# debug.net
KiCad netlist of a schematic drawn in Altium Designer
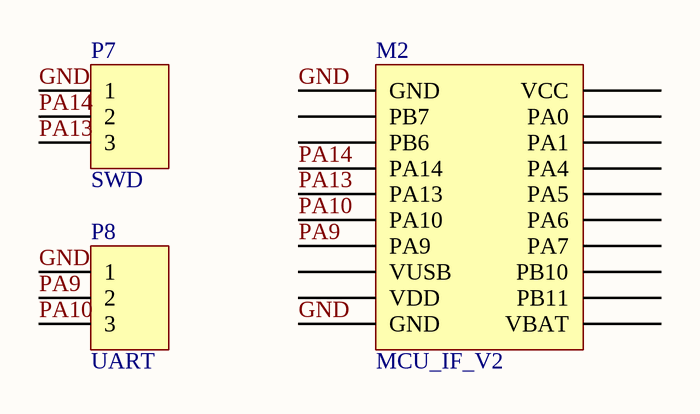
[diagram p0: debug.SchDoc]

(export (version "E")
  (design (tool "Eeschema 10.0.6"))
  (components
    (comp (ref "M2")
      (value "MCU_IF_V2")
      (footprint "MCU_IF_V2")
      (libsource (lib "MCU_IF") (part "MCU_IF_V1"))
    )
    (comp (ref "P7")
      (value "SWD")
      (footprint "EDGE_3_2.54")
      (description "Header, 3-Pin")
      (fields (field (name "PUBLISHER") "Altium Limited"))
      (libsource (lib "Miscellaneous Connectors") (part "Header 3"))
    )
    (comp (ref "P8")
      (value "UART")
      (footprint "EDGE_3_2.54")
      (description "Header, 3-Pin")
      (fields (field (name "PUBLISHER") "Altium Limited"))
      (libsource (lib "Miscellaneous Connectors") (part "Header 3"))
    )
  )
  (nets
    (net (code "1") (name "/GND") (class "Default")
      (node (ref "M2") (pin "1") (pinfunction "GND_1") (pintype "passive"))
      (node (ref "M2") (pin "10") (pinfunction "GND_10") (pintype "passive"))
      (node (ref "P7") (pin "1") (pinfunction "1_1") (pintype "passive"))
      (node (ref "P8") (pin "1") (pinfunction "1_1") (pintype "passive"))
    )
    (net (code "2") (name "/PA9") (class "Default")
      (node (ref "M2") (pin "7") (pinfunction "PA9_7") (pintype "passive"))
      (node (ref "P8") (pin "2") (pinfunction "2_2") (pintype "passive"))
    )
    (net (code "3") (name "/PA10") (class "Default")
      (node (ref "M2") (pin "6") (pinfunction "PA10_6") (pintype "passive"))
      (node (ref "P8") (pin "3") (pinfunction "3_3") (pintype "passive"))
    )
    (net (code "4") (name "/PA13") (class "Default")
      (node (ref "M2") (pin "5") (pinfunction "PA13_5") (pintype "passive"))
      (node (ref "P7") (pin "3") (pinfunction "3_3") (pintype "passive"))
    )
    (net (code "5") (name "/PA14") (class "Default")
      (node (ref "M2") (pin "4") (pinfunction "PA14_4") (pintype "passive"))
      (node (ref "P7") (pin "2") (pinfunction "2_2") (pintype "passive"))
    )
    (net (code "6") (name "unconnected-(M2-PA0-Pad19)") (class "Default")
      (node (ref "M2") (pin "19") (pinfunction "PA0_19") (pintype "passive"))
    )
    (net (code "7") (name "unconnected-(M2-PA1-Pad18)") (class "Default")
      (node (ref "M2") (pin "18") (pinfunction "PA1_18") (pintype "passive"))
    )
    (net (code "8") (name "unconnected-(M2-PA4-Pad17)") (class "Default")
      (node (ref "M2") (pin "17") (pinfunction "PA4_17") (pintype "passive"))
    )
    (net (code "9") (name "unconnected-(M2-PA5-Pad16)") (class "Default")
      (node (ref "M2") (pin "16") (pinfunction "PA5_16") (pintype "passive"))
    )
    (net (code "10") (name "unconnected-(M2-PA6-Pad15)") (class "Default")
      (node (ref "M2") (pin "15") (pinfunction "PA6_15") (pintype "passive"))
    )
    (net (code "11") (name "unconnected-(M2-PA7-Pad14)") (class "Default")
      (node (ref "M2") (pin "14") (pinfunction "PA7_14") (pintype "passive"))
    )
    (net (code "12") (name "unconnected-(M2-PB6-Pad3)") (class "Default")
      (node (ref "M2") (pin "3") (pinfunction "PB6_3") (pintype "passive"))
    )
    (net (code "13") (name "unconnected-(M2-PB7-Pad2)") (class "Default")
      (node (ref "M2") (pin "2") (pinfunction "PB7_2") (pintype "passive"))
    )
    (net (code "14") (name "unconnected-(M2-PB10-Pad13)") (class "Default")
      (node (ref "M2") (pin "13") (pinfunction "PB10_13") (pintype "passive"))
    )
    (net (code "15") (name "unconnected-(M2-PB11-Pad12)") (class "Default")
      (node (ref "M2") (pin "12") (pinfunction "PB11_12") (pintype "passive"))
    )
    (net (code "16") (name "unconnected-(M2-VBAT-Pad11)") (class "Default")
      (node (ref "M2") (pin "11") (pinfunction "VBAT_11") (pintype "passive"))
    )
    (net (code "17") (name "unconnected-(M2-VCC-Pad20)") (class "Default")
      (node (ref "M2") (pin "20") (pinfunction "VCC_20") (pintype "passive"))
    )
    (net (code "18") (name "unconnected-(M2-VDD-Pad9)") (class "Default")
      (node (ref "M2") (pin "9") (pinfunction "VDD_9") (pintype "passive"))
    )
    (net (code "19") (name "unconnected-(M2-VUSB-Pad8)") (class "Default")
      (node (ref "M2") (pin "8") (pinfunction "VUSB_8") (pintype "passive"))
    )
  )
)
